# telephon.net
KiCad netlist of a schematic drawn in EAGLE
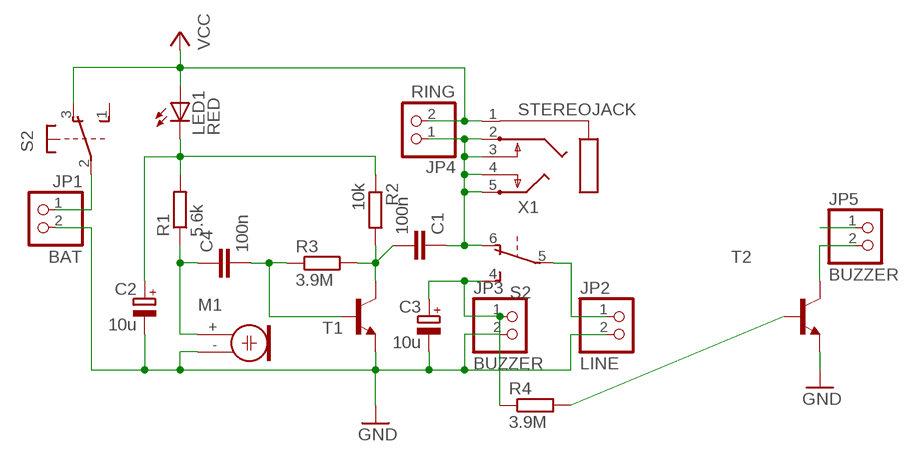
[diagram p0: schematic, sheet 1]

(export (version "E")
  (design (tool "Eeschema 10.0.6"))
  (components
    (comp (ref "C1")
      (value "100n")
      (footprint "eagle-import:C025-025X050")
      (libsource (lib "eagle-import") (part "C-EU025-025X050"))
    )
    (comp (ref "C2")
      (value "10u")
      (footprint "eagle-import:B45181A")
      (libsource (lib "eagle-import") (part "CPOL-EUB45181A"))
    )
    (comp (ref "C3")
      (value "10u")
      (footprint "eagle-import:B45181A")
      (libsource (lib "eagle-import") (part "CPOL-EUB45181A"))
    )
    (comp (ref "C4")
      (value "100n")
      (footprint "eagle-import:C025-025X050")
      (libsource (lib "eagle-import") (part "C-EU025-025X050"))
    )
    (comp (ref "JP1")
      (value "BAT")
      (footprint "eagle-import:1X02")
      (libsource (lib "eagle-import") (part "PINHD-1X2"))
    )
    (comp (ref "JP2")
      (value "LINE")
      (footprint "eagle-import:1X02")
      (libsource (lib "eagle-import") (part "PINHD-1X2"))
    )
    (comp (ref "JP3")
      (value "BUZZER")
      (footprint "eagle-import:1X02")
      (libsource (lib "eagle-import") (part "PINHD-1X2"))
    )
    (comp (ref "JP4")
      (value "RING")
      (footprint "eagle-import:1X02")
      (libsource (lib "eagle-import") (part "PINHD-1X2"))
    )
    (comp (ref "JP5")
      (value "BUZZER")
      (footprint "eagle-import:1X02")
      (libsource (lib "eagle-import") (part "PINHD-1X2"))
    )
    (comp (ref "LED1")
      (value "RED")
      (footprint "eagle-import:LED5MM")
      (libsource (lib "eagle-import") (part "LED5MM"))
    )
    (comp (ref "M1")
      (value "ELECTRET")
      (footprint "eagle-import:9.7ELECTRET")
      (libsource (lib "eagle-import") (part "ELECTRET"))
    )
    (comp (ref "R1")
      (value "5.6k")
      (footprint "eagle-import:0204_7")
      (libsource (lib "eagle-import") (part "R-EU_0204/7"))
    )
    (comp (ref "R2")
      (value "10k")
      (footprint "eagle-import:0204_7")
      (libsource (lib "eagle-import") (part "R-EU_0204/7"))
    )
    (comp (ref "R3")
      (value "3.9M")
      (footprint "eagle-import:0204_7")
      (libsource (lib "eagle-import") (part "R-EU_0204/7"))
    )
    (comp (ref "R4")
      (value "3.9M")
      (footprint "eagle-import:0204_7")
      (libsource (lib "eagle-import") (part "R-EU_0204/7"))
    )
    (comp (ref "S2")
      (value "9450-2")
      (footprint "eagle-import:9450-2")
      (libsource (lib "eagle-import") (part "9450-2"))
    )
    (comp (ref "T1")
      (value "BC547-NPN-TO92-CBE")
      (footprint "eagle-import:TO92-CBE")
      (libsource (lib "eagle-import") (part "-NPN-TO92-CBEBC547"))
    )
    (comp (ref "T2")
      (value "BC547-NPN-TO92-CBE")
      (footprint "eagle-import:TO92-CBE")
      (libsource (lib "eagle-import") (part "-NPN-TO92-CBEBC547"))
    )
    (comp (ref "X1")
      (value "STEREOJACK")
      (footprint "eagle-import:STX3100")
      (libsource (lib "eagle-import") (part "STEREOJACK"))
    )
  )
  (nets
    (net (code "1") (name "GND") (class "Default")
      (node (ref "C2") (pin "-") (pinfunction "-_-") (pintype "passive"))
      (node (ref "C3") (pin "-") (pinfunction "-_-") (pintype "passive"))
      (node (ref "JP1") (pin "2") (pinfunction "2_2") (pintype "passive"))
      (node (ref "JP2") (pin "2") (pinfunction "2_2") (pintype "passive"))
      (node (ref "JP3") (pin "2") (pinfunction "2_2") (pintype "passive"))
      (node (ref "M1") (pin "-") (pinfunction "1_-") (pintype "passive"))
      (node (ref "T1") (pin "E") (pinfunction "E_E") (pintype "passive"))
      (node (ref "T2") (pin "E") (pinfunction "E_E") (pintype "passive"))
    )
    (net (code "2") (name "Net-(C1-Pad2)") (class "Default")
      (node (ref "C1") (pin "2") (pinfunction "2_2") (pintype "passive"))
      (node (ref "R2") (pin "2") (pinfunction "2_2") (pintype "passive"))
      (node (ref "R3") (pin "2") (pinfunction "2_2") (pintype "passive"))
      (node (ref "T1") (pin "C") (pinfunction "C_C") (pintype "passive"))
    )
    (net (code "3") (name "Net-(C4-Pad2)") (class "Default")
      (node (ref "C4") (pin "2") (pinfunction "2_2") (pintype "passive"))
      (node (ref "R3") (pin "1") (pinfunction "1_1") (pintype "passive"))
      (node (ref "T1") (pin "B") (pinfunction "B_B") (pintype "passive"))
    )
    (net (code "4") (name "Net-(JP5-Pad2)") (class "Default")
      (node (ref "JP5") (pin "2") (pinfunction "2_2") (pintype "passive"))
      (node (ref "T2") (pin "C") (pinfunction "C_C") (pintype "passive"))
    )
    (net (code "5") (name "Net-(LED1-C)") (class "Default")
      (node (ref "C2") (pin "+") (pinfunction "+_+") (pintype "passive"))
      (node (ref "LED1") (pin "K") (pinfunction "C_K") (pintype "passive"))
      (node (ref "R1") (pin "2") (pinfunction "2_2") (pintype "passive"))
      (node (ref "R2") (pin "1") (pinfunction "1_1") (pintype "passive"))
    )
    (net (code "6") (name "Net-(M1-2)") (class "Default")
      (node (ref "C4") (pin "1") (pinfunction "1_1") (pintype "passive"))
      (node (ref "M1") (pin "+") (pinfunction "2_+") (pintype "passive"))
      (node (ref "R1") (pin "1") (pinfunction "1_1") (pintype "passive"))
    )
    (net (code "7") (name "Net-(R4-Pad2)") (class "Default")
      (node (ref "R4") (pin "2") (pinfunction "2_2") (pintype "passive"))
      (node (ref "T2") (pin "B") (pinfunction "B_B") (pintype "passive"))
    )
    (net (code "8") (name "Net-(S2A-P)") (class "Default")
      (node (ref "JP1") (pin "1") (pinfunction "1_1") (pintype "passive"))
      (node (ref "S2") (pin "2") (pinfunction "P_2") (pintype "passive"))
    )
    (net (code "9") (name "Net-(S2B-O)") (class "Default")
      (node (ref "C1") (pin "1") (pinfunction "1_1") (pintype "passive"))
      (node (ref "JP4") (pin "1") (pinfunction "1_1") (pintype "passive"))
      (node (ref "S2") (pin "6") (pinfunction "O_6") (pintype "passive"))
      (node (ref "X1") (pin "2") (pinfunction "2_2") (pintype "passive"))
      (node (ref "X1") (pin "3") (pinfunction "3_3") (pintype "passive"))
      (node (ref "X1") (pin "4") (pinfunction "4_4") (pintype "passive"))
      (node (ref "X1") (pin "5") (pinfunction "5_5") (pintype "passive"))
    )
    (net (code "10") (name "Net-(S2B-P)") (class "Default")
      (node (ref "JP2") (pin "1") (pinfunction "1_1") (pintype "passive"))
      (node (ref "S2") (pin "5") (pinfunction "P_5") (pintype "passive"))
    )
    (net (code "11") (name "Net-(S2B-S)") (class "Default")
      (node (ref "C3") (pin "+") (pinfunction "+_+") (pintype "passive"))
      (node (ref "JP3") (pin "1") (pinfunction "1_1") (pintype "passive"))
      (node (ref "R4") (pin "1") (pinfunction "1_1") (pintype "passive"))
      (node (ref "S2") (pin "4") (pinfunction "S_4") (pintype "passive"))
    )
    (net (code "12") (name "VCC") (class "Default")
      (node (ref "JP4") (pin "2") (pinfunction "2_2") (pintype "passive"))
      (node (ref "LED1") (pin "A") (pinfunction "A_A") (pintype "passive"))
      (node (ref "S2") (pin "3") (pinfunction "O_3") (pintype "passive"))
      (node (ref "X1") (pin "1") (pinfunction "1_1") (pintype "passive"))
    )
    (net (code "13") (name "unconnected-(JP5-Pad1)") (class "Default")
      (node (ref "JP5") (pin "1") (pinfunction "1_1") (pintype "passive"))
    )
    (net (code "14") (name "unconnected-(S2A-S-Pad1)") (class "Default")
      (node (ref "S2") (pin "1") (pinfunction "S_1") (pintype "passive"))
    )
  )
)
